# dc_power_module_v1.net
KiCad netlist of a schematic drawn in Altium Designer
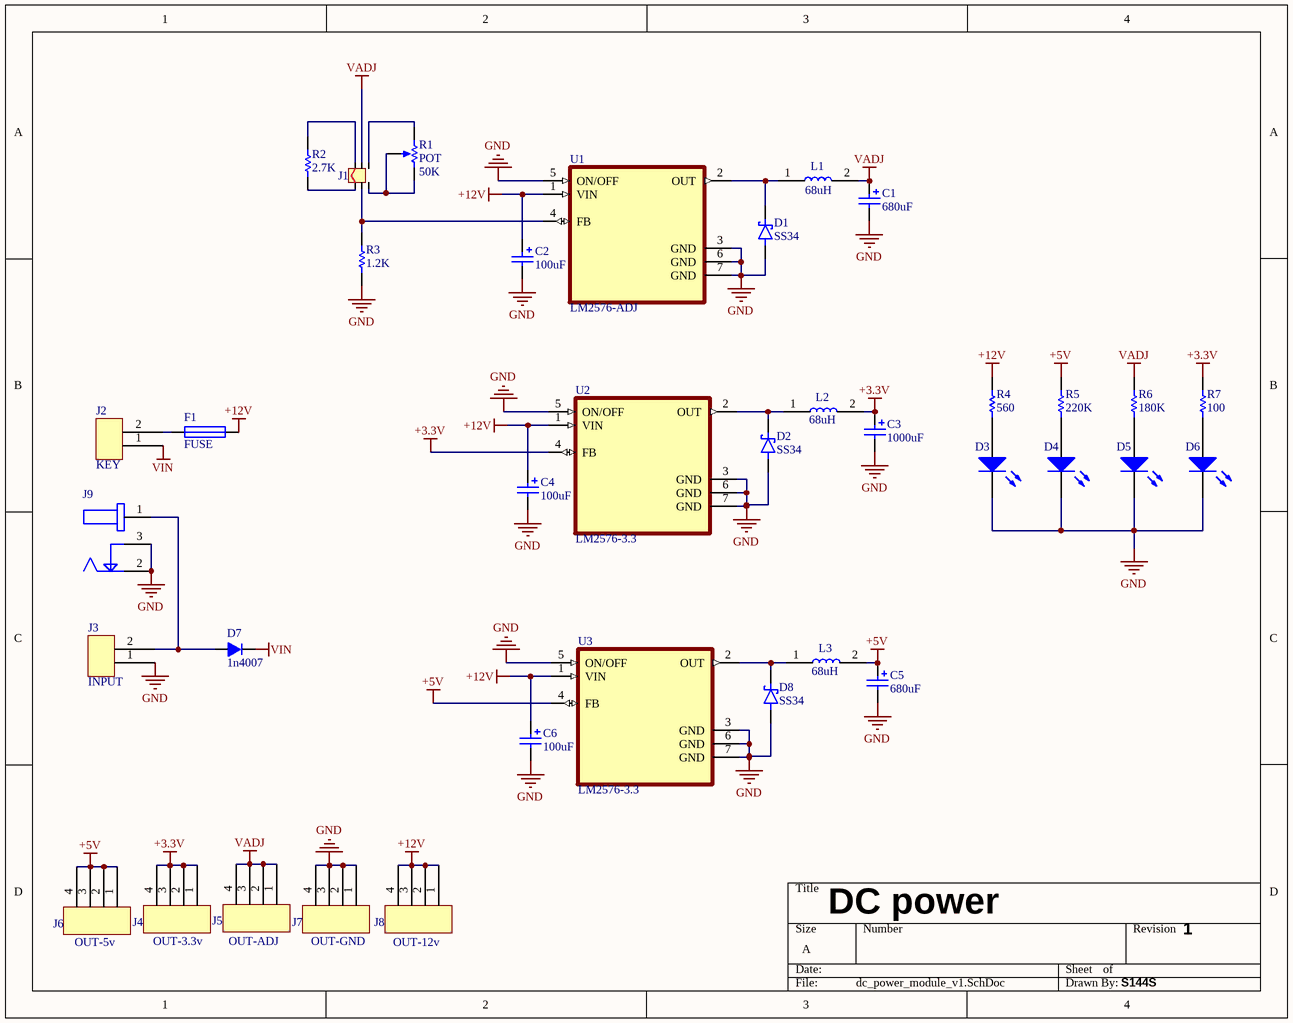
[diagram p0: dc_power_module_v1.SchDoc]

(export (version "E")
  (design (tool "Eeschema 10.0.6"))
  (components
    (comp (ref "C1")
      (value "680uF")
      (footprint "Cap 03")
      (description "Polarized Capacitor (Axial)")
      (fields (field (name "Comment") "Cap Pol2") (field (name "PUBLISHER") "Altium Limited"))
      (libsource (lib "Miscellaneous Devices") (part "Cap Pol2"))
    )
    (comp (ref "C2")
      (value "100uF")
      (footprint "Cap - 470uF")
      (description "Polarized Capacitor (Axial)")
      (fields (field (name "Comment") "Cap Pol2") (field (name "PUBLISHER") "Altium Limited"))
      (libsource (lib "Miscellaneous Devices") (part "Cap Pol2"))
    )
    (comp (ref "C3")
      (value "1000uF")
      (footprint "Cap 04")
      (description "Polarized Capacitor (Axial)")
      (fields (field (name "Comment") "Cap Pol2") (field (name "PUBLISHER") "Altium Limited"))
      (libsource (lib "Miscellaneous Devices") (part "Cap Pol2"))
    )
    (comp (ref "C4")
      (value "100uF")
      (footprint "Cap - 470uF")
      (description "Polarized Capacitor (Axial)")
      (fields (field (name "Comment") "Cap Pol2") (field (name "PUBLISHER") "Altium Limited"))
      (libsource (lib "Miscellaneous Devices") (part "Cap Pol2"))
    )
    (comp (ref "C5")
      (value "680uF")
      (footprint "Cap 03")
      (description "Polarized Capacitor (Axial)")
      (fields (field (name "Comment") "Cap Pol2") (field (name "PUBLISHER") "Altium Limited"))
      (libsource (lib "Miscellaneous Devices") (part "Cap Pol2"))
    )
    (comp (ref "C6")
      (value "100uF")
      (footprint "Cap - 470uF")
      (description "Polarized Capacitor (Axial)")
      (fields (field (name "Comment") "Cap Pol2") (field (name "PUBLISHER") "Altium Limited"))
      (libsource (lib "Miscellaneous Devices") (part "Cap Pol2"))
    )
    (comp (ref "D1")
      (value "SS34")
      (footprint "DIOM7959X262N")
      (description "Diode Schottky 40V 3A Surface Mount DO-214AB _SMC_")
      (fields (field (name "MP") "SS34-E3/57T") (field (name "MF") "Vishay"))
      (libsource (lib "SS34-AB") (part "SS34-E3/57T"))
    )
    (comp (ref "D2")
      (value "SS34")
      (footprint "DIOM7959X262N")
      (description "Diode Schottky 40V 3A Surface Mount DO-214AB _SMC_")
      (fields (field (name "MP") "SS34-E3/57T") (field (name "MF") "Vishay"))
      (libsource (lib "SS34-AB") (part "SS34-E3/57T"))
    )
    (comp (ref "D3")
      (value "LED1")
      (footprint "LED SMD 1206")
      (description "Typical RED GaAs LED")
      (fields (field (name "PUBLISHER") "Altium Limited"))
      (libsource (lib "Miscellaneous Devices") (part "LED1"))
    )
    (comp (ref "D4")
      (value "LED1")
      (footprint "LED SMD 1206")
      (description "Typical RED GaAs LED")
      (fields (field (name "PUBLISHER") "Altium Limited"))
      (libsource (lib "Miscellaneous Devices") (part "LED1"))
    )
    (comp (ref "D5")
      (value "LED1")
      (footprint "LED SMD 1206")
      (description "Typical RED GaAs LED")
      (fields (field (name "PUBLISHER") "Altium Limited"))
      (libsource (lib "Miscellaneous Devices") (part "LED1"))
    )
    (comp (ref "D6")
      (value "LED1")
      (footprint "LED SMD 1206")
      (description "Typical RED GaAs LED")
      (fields (field (name "PUBLISHER") "Altium Limited"))
      (libsource (lib "Miscellaneous Devices") (part "LED1"))
    )
    (comp (ref "D7")
      (value "1n4007")
      (footprint "DIODE_4001")
      (description "Rectifire Diode")
      (libsource (lib "JJ_S1") (part "DIOD"))
    )
    (comp (ref "D8")
      (value "SS34")
      (footprint "DIOM7959X262N")
      (description "Diode Schottky 40V 3A Surface Mount DO-214AB _SMC_")
      (fields (field (name "MP") "SS34-E3/57T") (field (name "MF") "Vishay"))
      (libsource (lib "SS34-AB") (part "SS34-E3/57T"))
    )
    (comp (ref "F1") (value "FUSE") (footprint "Fuse - Complex") (libsource (lib "JJ_S1") (part "FUSE")))
    (comp (ref "J1")
      (value "JUMPER6")
      (footprint "JUMP6")
      (description "Ju,per & dip Switch")
      (libsource (lib "JJ_S1") (part "JUMPER6"))
    )
    (comp (ref "J2") (value "KEY") (footprint "SIP2") (libsource (lib "JJ_S1") (part "2PIN")))
    (comp (ref "J3") (value "INPUT") (footprint "SIP2") (libsource (lib "JJ_S1") (part "2PIN")))
    (comp (ref "J4") (value "OUT-3.3v") (footprint "SIP4") (libsource (lib "JJ_S1") (part "4PIN")))
    (comp (ref "J5") (value "OUT-ADJ") (footprint "SIP4") (libsource (lib "JJ_S1") (part "4PIN")))
    (comp (ref "J6") (value "OUT-5v") (footprint "SIP4") (libsource (lib "JJ_S1") (part "4PIN")))
    (comp (ref "J7") (value "OUT-GND") (footprint "SIP4") (libsource (lib "JJ_S1") (part "4PIN")))
    (comp (ref "J8") (value "OUT-12v") (footprint "SIP4") (libsource (lib "JJ_S1") (part "4PIN")))
    (comp (ref "J9")
      (value "DCJ250-10-A_XX-X_REVA")
      (footprint "Power Jack")
      (description "Power Barrel Connector Jack 2.55mm ID _0.100_, 5.50mm OD _0.217_ Through Hole, Right Angle")
      (fields (field (name "MP") "DCJ250-10-A-K1-K") (field (name "MF") "Global Connector Technology"))
      (libsource (lib "Power-Jack") (part "DCJ250-10-A_XX-X_REVA"))
    )
    (comp (ref "L1")
      (value "68uH")
      (footprint "*IND_SRP1265A-330M")
      (description "Inductor Power Shielded Wirewound 33uH 20% 100KHz Carbonyl Powder 8A 58mOhm DCR Automotive T/R")
      (fields (field (name "MF") "Bourns") (field (name "MP") "SRP1265A-330M"))
      (libsource (lib "33uH-Inductor") (part "SRP1265A-330M"))
    )
    (comp (ref "L2")
      (value "68uH")
      (footprint "*IND_SRP1265A-330M")
      (description "Inductor Power Shielded Wirewound 33uH 20% 100KHz Carbonyl Powder 8A 58mOhm DCR Automotive T/R")
      (fields (field (name "MF") "Bourns") (field (name "MP") "SRP1265A-330M"))
      (libsource (lib "33uH-Inductor") (part "SRP1265A-330M"))
    )
    (comp (ref "L3")
      (value "68uH")
      (footprint "*IND_SRP1265A-330M")
      (description "Inductor Power Shielded Wirewound 33uH 20% 100KHz Carbonyl Powder 8A 58mOhm DCR Automotive T/R")
      (fields (field (name "MF") "Bourns") (field (name "MP") "SRP1265A-330M"))
      (libsource (lib "33uH-Inductor") (part "SRP1265A-330M"))
    )
    (comp (ref "R1")
      (value "POT")
      (footprint "Pot 00")
      (description "Volume Potentiometer")
      (fields (field (name "ALTIUM_VALUE") "50K") (field (name "PUBLISHER") "Altium Limited"))
      (libsource (lib "Ario Electronics ALTLIB") (part "RPot"))
    )
    (comp (ref "R2")
      (value "2.7K")
      (footprint "RES 1206")
      (description "Resistor")
      (fields (field (name "Comment") "Res-1206") (field (name "PUBLISHER") "Altium Limited"))
      (libsource (lib "Ario Electronics ALTLIB") (part "Res-1206"))
    )
    (comp (ref "R3")
      (value "1.2K")
      (footprint "RES 1206")
      (description "Resistor")
      (fields (field (name "Comment") "Res-1206") (field (name "PUBLISHER") "Altium Limited"))
      (libsource (lib "Ario Electronics ALTLIB") (part "Res-1206"))
    )
    (comp (ref "R4")
      (value "560")
      (footprint "RES 1206")
      (description "Resistor")
      (fields (field (name "Comment") "Res-1206") (field (name "PUBLISHER") "Altium Limited"))
      (libsource (lib "Ario Electronics ALTLIB") (part "Res-1206"))
    )
    (comp (ref "R5")
      (value "220K")
      (footprint "RES 1206")
      (description "Resistor")
      (fields (field (name "Comment") "Res-1206") (field (name "PUBLISHER") "Altium Limited"))
      (libsource (lib "Ario Electronics ALTLIB") (part "Res-1206"))
    )
    (comp (ref "R6")
      (value "180K")
      (footprint "RES 1206")
      (description "Resistor")
      (fields (field (name "Comment") "Res-1206") (field (name "PUBLISHER") "Altium Limited"))
      (libsource (lib "Ario Electronics ALTLIB") (part "Res-1206"))
    )
    (comp (ref "R7")
      (value "100")
      (footprint "RES 1206")
      (description "Resistor")
      (fields (field (name "Comment") "Res-1206") (field (name "PUBLISHER") "Altium Limited"))
      (libsource (lib "Ario Electronics ALTLIB") (part "Res-1206"))
    )
    (comp (ref "U1")
      (value "LM2576-ADJ")
      (footprint "VREG_TPS79625KTTR")
      (fields
        (field (name "MP") "LM2576HVS-ADJ/NOPB")
        (field (name "MF") "Texas Instruments")
        (field (name "BUYPART") "https://www.snapeda.com/parts/LM2576HVS-ADJ/NOPB/Texas%20Instruments/view-part/213619/?ref=eda")
      )
      (libsource (lib "LM2576HVS-ADJ_NOPB") (part "LM2576HVS-ADJ/NOPB"))
    )
    (comp (ref "U2")
      (value "LM2576-3.3")
      (footprint "VREG_TPS79625KTTR")
      (fields
        (field (name "MP") "LM2576HVS-ADJ/NOPB")
        (field (name "MF") "Texas Instruments")
        (field (name "BUYPART") "https://www.snapeda.com/parts/LM2576HVS-ADJ/NOPB/Texas%20Instruments/view-part/213619/?ref=eda")
      )
      (libsource (lib "LM2576HVS-ADJ_NOPB") (part "LM2576HVS-ADJ/NOPB"))
    )
    (comp (ref "U3")
      (value "LM2576-3.3")
      (footprint "VREG_TPS79625KTTR")
      (fields
        (field (name "MP") "LM2576HVS-ADJ/NOPB")
        (field (name "MF") "Texas Instruments")
        (field (name "BUYPART") "https://www.snapeda.com/parts/LM2576HVS-ADJ/NOPB/Texas%20Instruments/view-part/213619/?ref=eda")
      )
      (libsource (lib "LM2576HVS-ADJ_NOPB") (part "LM2576HVS-ADJ/NOPB"))
    )
  )
  (nets
    (net (code "1") (name "+3.3V") (class "Default")
      (node (ref "C3") (pin "1") (pinfunction "1_1") (pintype "passive"))
      (node (ref "J4") (pin "1") (pintype "passive"))
      (node (ref "J4") (pin "2") (pintype "passive"))
      (node (ref "J4") (pin "3") (pintype "passive"))
      (node (ref "J4") (pin "4") (pintype "passive"))
      (node (ref "L2") (pin "2") (pinfunction "2_2") (pintype "passive"))
      (node (ref "R7") (pin "2") (pinfunction "2_2") (pintype "passive"))
      (node (ref "U2") (pin "4") (pinfunction "FB_4") (pintype "bidirectional"))
    )
    (net (code "2") (name "+5V") (class "Default")
      (node (ref "C5") (pin "1") (pinfunction "1_1") (pintype "passive"))
      (node (ref "J6") (pin "1") (pintype "passive"))
      (node (ref "J6") (pin "2") (pintype "passive"))
      (node (ref "J6") (pin "3") (pintype "passive"))
      (node (ref "J6") (pin "4") (pintype "passive"))
      (node (ref "L3") (pin "2") (pinfunction "2_2") (pintype "passive"))
      (node (ref "R5") (pin "2") (pinfunction "2_2") (pintype "passive"))
      (node (ref "U3") (pin "4") (pinfunction "FB_4") (pintype "bidirectional"))
    )
    (net (code "3") (name "+12V") (class "Default")
      (node (ref "C2") (pin "1") (pinfunction "1_1") (pintype "passive"))
      (node (ref "C4") (pin "1") (pinfunction "1_1") (pintype "passive"))
      (node (ref "C6") (pin "1") (pinfunction "1_1") (pintype "passive"))
      (node (ref "F1") (pin "2") (pintype "passive"))
      (node (ref "J8") (pin "1") (pintype "passive"))
      (node (ref "J8") (pin "2") (pintype "passive"))
      (node (ref "J8") (pin "3") (pintype "passive"))
      (node (ref "J8") (pin "4") (pintype "passive"))
      (node (ref "R4") (pin "2") (pinfunction "2_2") (pintype "passive"))
      (node (ref "U1") (pin "1") (pinfunction "VIN_1") (pintype "input"))
      (node (ref "U2") (pin "1") (pinfunction "VIN_1") (pintype "input"))
      (node (ref "U3") (pin "1") (pinfunction "VIN_1") (pintype "input"))
    )
    (net (code "4") (name "GND") (class "Default")
      (node (ref "C1") (pin "2") (pinfunction "2_2") (pintype "passive"))
      (node (ref "C2") (pin "2") (pinfunction "2_2") (pintype "passive"))
      (node (ref "C3") (pin "2") (pinfunction "2_2") (pintype "passive"))
      (node (ref "C4") (pin "2") (pinfunction "2_2") (pintype "passive"))
      (node (ref "C5") (pin "2") (pinfunction "2_2") (pintype "passive"))
      (node (ref "C6") (pin "2") (pinfunction "2_2") (pintype "passive"))
      (node (ref "D1") (pin "A") (pinfunction "A_A") (pintype "passive"))
      (node (ref "D2") (pin "A") (pinfunction "A_A") (pintype "passive"))
      (node (ref "D3") (pin "2") (pinfunction "K_2") (pintype "passive"))
      (node (ref "D4") (pin "2") (pinfunction "K_2") (pintype "passive"))
      (node (ref "D5") (pin "2") (pinfunction "K_2") (pintype "passive"))
      (node (ref "D6") (pin "2") (pinfunction "K_2") (pintype "passive"))
      (node (ref "D8") (pin "A") (pinfunction "A_A") (pintype "passive"))
      (node (ref "J3") (pin "1") (pintype "passive"))
      (node (ref "J7") (pin "1") (pintype "passive"))
      (node (ref "J7") (pin "2") (pintype "passive"))
      (node (ref "J7") (pin "3") (pintype "passive"))
      (node (ref "J7") (pin "4") (pintype "passive"))
      (node (ref "J9") (pin "2") (pinfunction "2_2") (pintype "passive"))
      (node (ref "J9") (pin "3") (pinfunction "3_3") (pintype "passive"))
      (node (ref "R3") (pin "1") (pinfunction "1_1") (pintype "passive"))
      (node (ref "U1") (pin "3") (pinfunction "GND_3") (pintype "power_in"))
      (node (ref "U1") (pin "5") (pinfunction "ON/OFF_5") (pintype "input"))
      (node (ref "U1") (pin "6") (pinfunction "GND_6") (pintype "power_in"))
      (node (ref "U1") (pin "7") (pinfunction "GND_7") (pintype "power_in"))
      (node (ref "U2") (pin "3") (pinfunction "GND_3") (pintype "power_in"))
      (node (ref "U2") (pin "5") (pinfunction "ON/OFF_5") (pintype "input"))
      (node (ref "U2") (pin "6") (pinfunction "GND_6") (pintype "power_in"))
      (node (ref "U2") (pin "7") (pinfunction "GND_7") (pintype "power_in"))
      (node (ref "U3") (pin "3") (pinfunction "GND_3") (pintype "power_in"))
      (node (ref "U3") (pin "5") (pinfunction "ON/OFF_5") (pintype "input"))
      (node (ref "U3") (pin "6") (pinfunction "GND_6") (pintype "power_in"))
      (node (ref "U3") (pin "7") (pinfunction "GND_7") (pintype "power_in"))
    )
    (net (code "5") (name "Net-(D3-A)") (class "Default")
      (node (ref "D3") (pin "1") (pinfunction "A_1") (pintype "passive"))
      (node (ref "R4") (pin "1") (pinfunction "1_1") (pintype "passive"))
    )
    (net (code "6") (name "Net-(D4-A)") (class "Default")
      (node (ref "D4") (pin "1") (pinfunction "A_1") (pintype "passive"))
      (node (ref "R5") (pin "1") (pinfunction "1_1") (pintype "passive"))
    )
    (net (code "7") (name "Net-(D5-A)") (class "Default")
      (node (ref "D5") (pin "1") (pinfunction "A_1") (pintype "passive"))
      (node (ref "R6") (pin "1") (pinfunction "1_1") (pintype "passive"))
    )
    (net (code "8") (name "Net-(D6-A)") (class "Default")
      (node (ref "D6") (pin "1") (pinfunction "A_1") (pintype "passive"))
      (node (ref "R7") (pin "1") (pinfunction "1_1") (pintype "passive"))
    )
    (net (code "9") (name "Net-(D7-A)") (class "Default")
      (node (ref "D7") (pin "1") (pinfunction "A_1") (pintype "passive"))
      (node (ref "J3") (pin "2") (pintype "passive"))
      (node (ref "J9") (pin "1") (pinfunction "1_1") (pintype "passive"))
    )
    (net (code "10") (name "Net-(F1-Pad1)") (class "Default")
      (node (ref "F1") (pin "1") (pintype "passive"))
      (node (ref "J2") (pin "2") (pintype "passive"))
    )
    (net (code "11") (name "Net-(J1-Pad1)") (class "Default")
      (node (ref "J1") (pin "1") (pintype "passive"))
      (node (ref "R2") (pin "1") (pinfunction "1_1") (pintype "passive"))
    )
    (net (code "12") (name "Net-(J1-Pad2)") (class "Default")
      (node (ref "J1") (pin "2") (pintype "passive"))
      (node (ref "R2") (pin "2") (pinfunction "2_2") (pintype "passive"))
    )
    (net (code "13") (name "Net-(R1-BOT)") (class "Default")
      (node (ref "J1") (pin "5") (pintype "passive"))
      (node (ref "R1") (pin "2") (pinfunction "BOT_2") (pintype "passive"))
      (node (ref "R1") (pin "3") (pinfunction "TAP_3") (pintype "passive"))
    )
    (net (code "14") (name "Net-(R1-TOP)") (class "Default")
      (node (ref "J1") (pin "6") (pintype "passive"))
      (node (ref "R1") (pin "1") (pinfunction "TOP_1") (pintype "passive"))
    )
    (net (code "15") (name "Net-(U1-FB)") (class "Default")
      (node (ref "J1") (pin "3") (pintype "passive"))
      (node (ref "R3") (pin "2") (pinfunction "2_2") (pintype "passive"))
      (node (ref "U1") (pin "4") (pinfunction "FB_4") (pintype "bidirectional"))
    )
    (net (code "16") (name "Net-(U1-OUT)") (class "Default")
      (node (ref "D1") (pin "C") (pinfunction "C_C") (pintype "passive"))
      (node (ref "L1") (pin "1") (pinfunction "1_1") (pintype "passive"))
      (node (ref "U1") (pin "2") (pinfunction "OUT_2") (pintype "output"))
    )
    (net (code "17") (name "Net-(U2-OUT)") (class "Default")
      (node (ref "D2") (pin "C") (pinfunction "C_C") (pintype "passive"))
      (node (ref "L2") (pin "1") (pinfunction "1_1") (pintype "passive"))
      (node (ref "U2") (pin "2") (pinfunction "OUT_2") (pintype "output"))
    )
    (net (code "18") (name "Net-(U3-OUT)") (class "Default")
      (node (ref "D8") (pin "C") (pinfunction "C_C") (pintype "passive"))
      (node (ref "L3") (pin "1") (pinfunction "1_1") (pintype "passive"))
      (node (ref "U3") (pin "2") (pinfunction "OUT_2") (pintype "output"))
    )
    (net (code "19") (name "VADJ") (class "Default")
      (node (ref "C1") (pin "1") (pinfunction "1_1") (pintype "passive"))
      (node (ref "J1") (pin "4") (pintype "passive"))
      (node (ref "J5") (pin "1") (pintype "passive"))
      (node (ref "J5") (pin "2") (pintype "passive"))
      (node (ref "J5") (pin "3") (pintype "passive"))
      (node (ref "J5") (pin "4") (pintype "passive"))
      (node (ref "L1") (pin "2") (pinfunction "2_2") (pintype "passive"))
      (node (ref "R6") (pin "2") (pinfunction "2_2") (pintype "passive"))
    )
    (net (code "20") (name "VIN") (class "Default")
      (node (ref "D7") (pin "2") (pinfunction "K_2") (pintype "passive"))
      (node (ref "J2") (pin "1") (pintype "passive"))
    )
  )
)
